# MAX96717_EVB_revC.net
KiCad netlist of a schematic drawn in Altium Designer
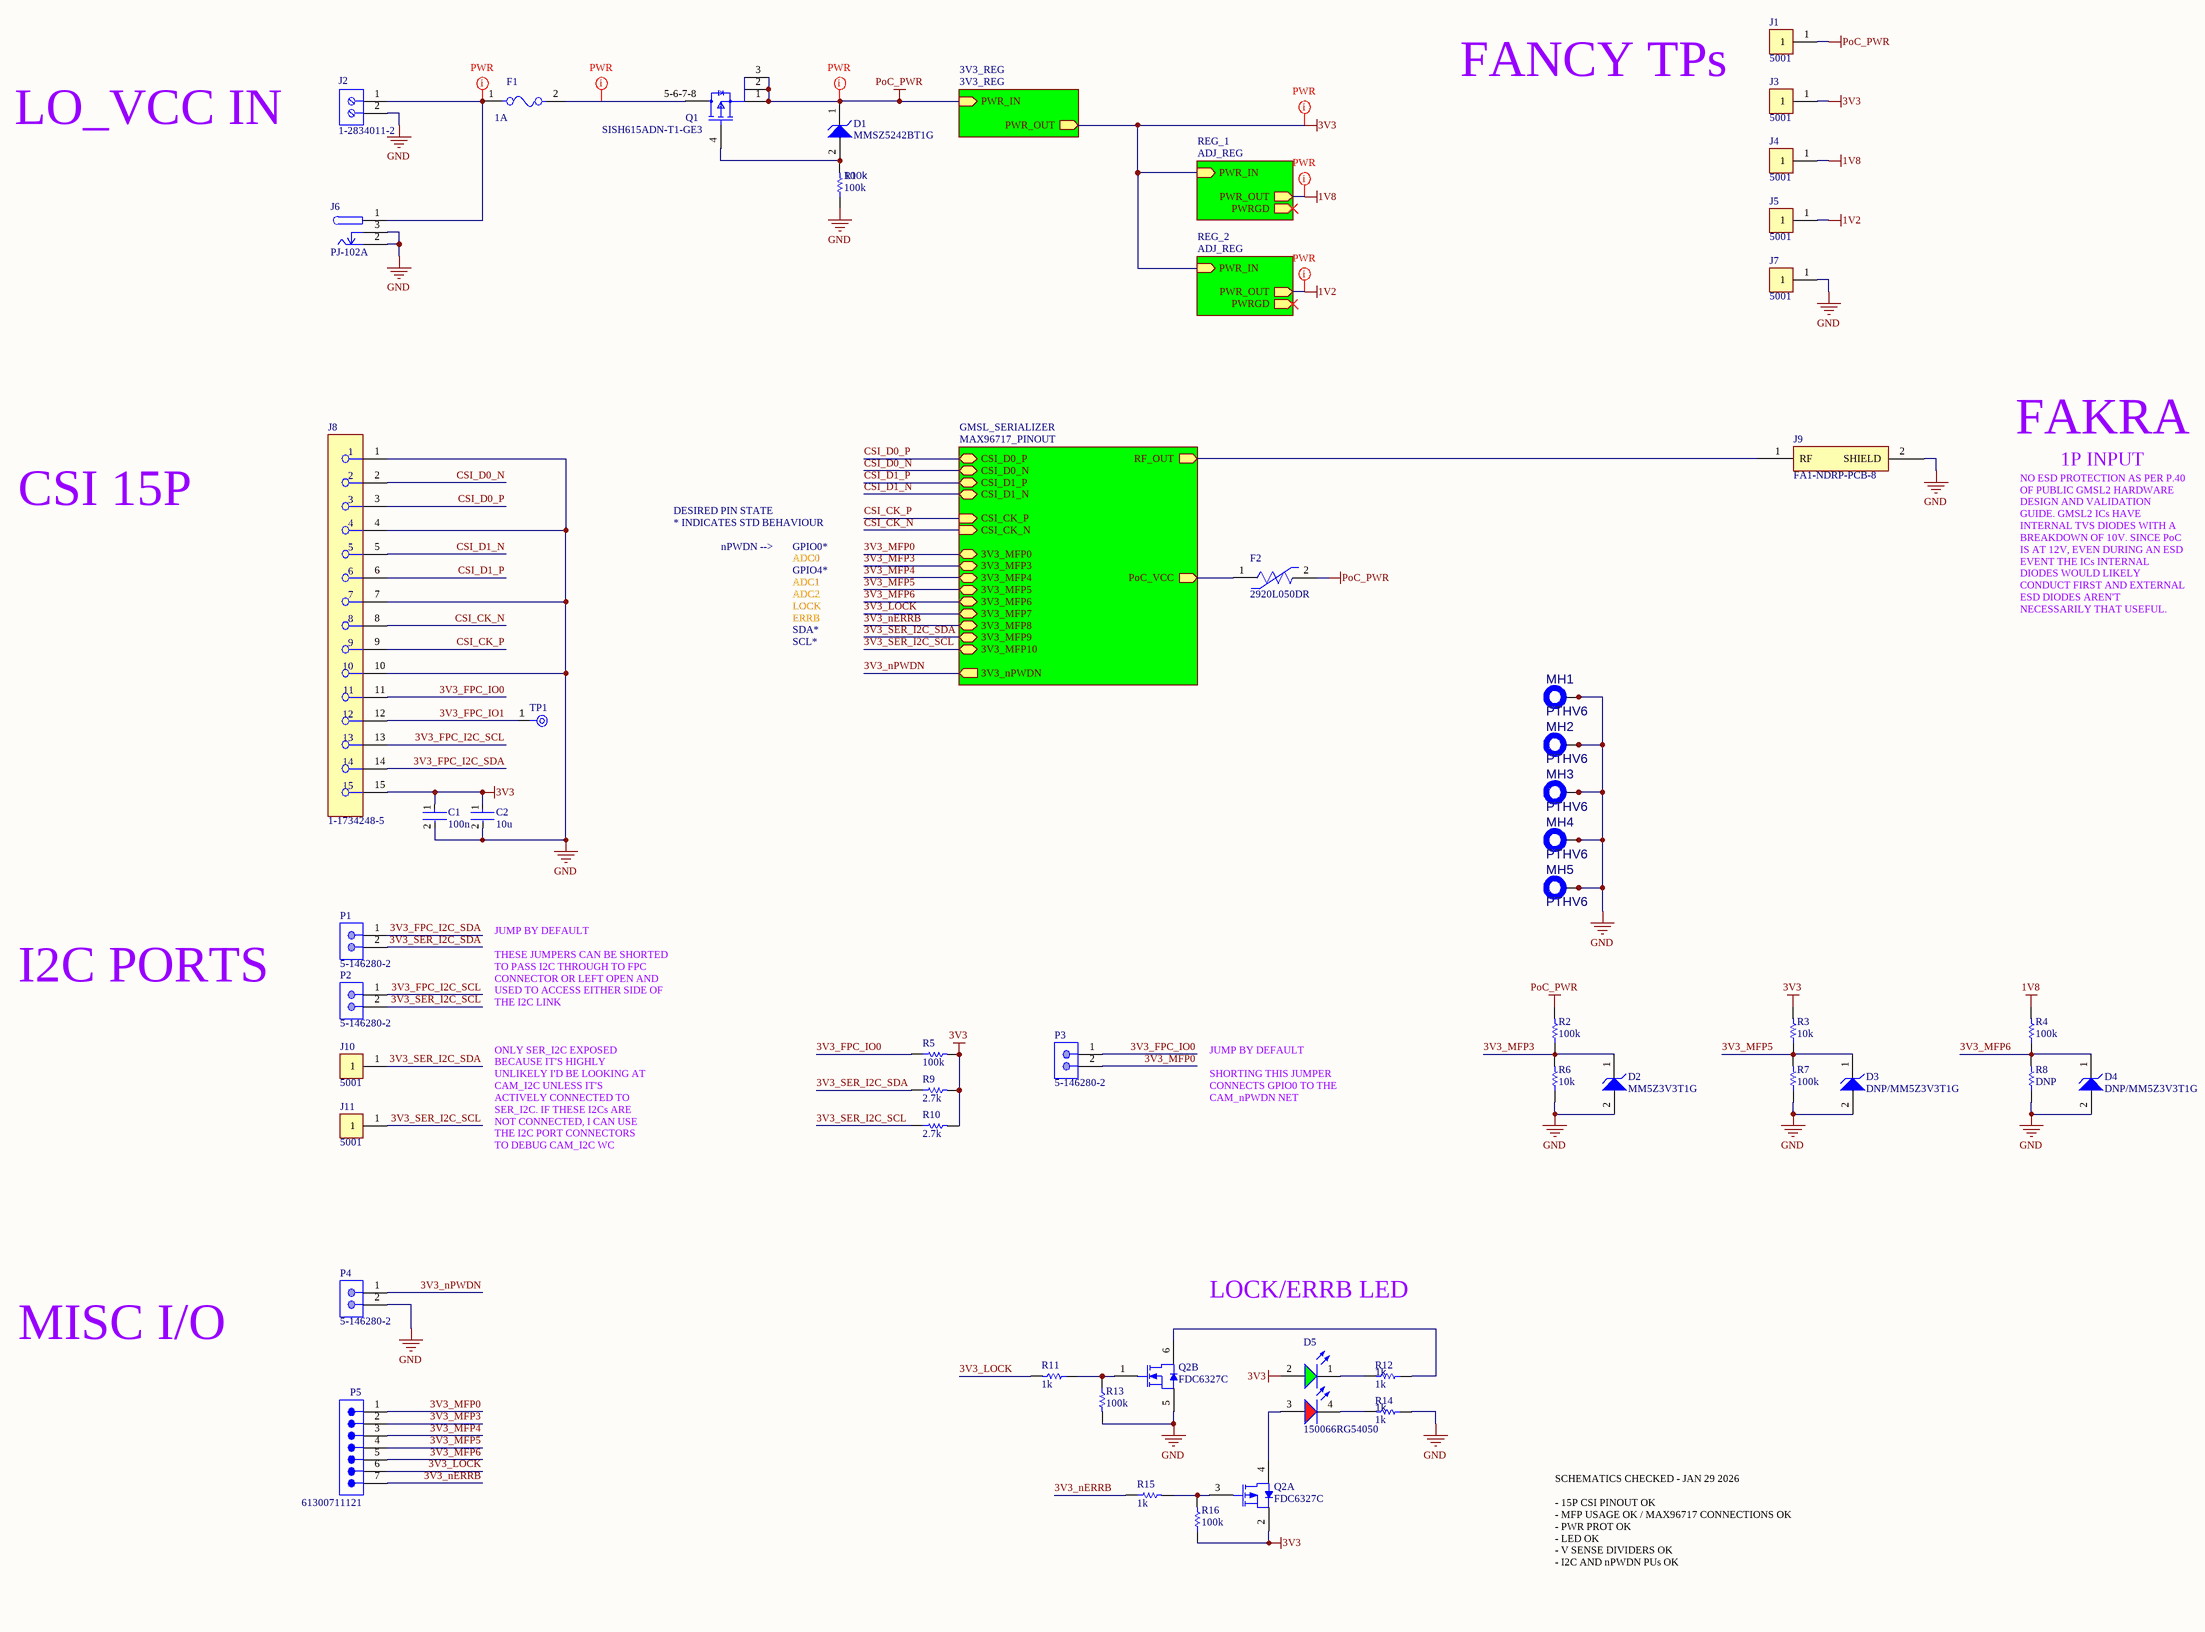
[diagram p0: MAX96717_EVB_revC.SchDoc]

(export (version "E")
  (design (tool "Eeschema 10.0.6"))
  (components
    (comp (ref "C1")
      (value "100n")
      (footprint "FP-0402-L_1_0_0_05-W_0_5-IPC_A")
      (description "LARGE PADS, 0402 CAP, CHANGE COMMENT TO MATCH REAL P/N")
      (libsource (lib "Space Concordia") (part "b4654b650e69147ec39a6b967a45e02"))
    )
    (comp (ref "C2")
      (value "10u")
      (footprint "FP-0402-L_1_0_0_05-W_0_5-IPC_A")
      (description "LARGE PADS, 0402 CAP, CHANGE COMMENT TO MATCH REAL P/N")
      (libsource (lib "Space Concordia") (part "b4654b650e69147ec39a6b967a45e02"))
    )
    (comp (ref "D1")
      (value "MMSZ5242BT1G")
      (footprint "ONSC-SOD-123-2-425-04_V")
      (description "Zener Voltage Regulator, 500 mW, 2-Pin SOD-123, Pb-Free, Tape and Reel")
      (fields (field (name "MANUFACTURER") "On Semiconductor"))
      (libsource (lib "Altium Content Vault") (part "ONSC-K1A2-2"))
    )
    (comp (ref "D2")
      (value "MM5Z3V3T1G")
      (footprint "ONSC-SOD-523-2-502-01_V")
      (description "Zener Voltage Regulator, 500 mW, 2-Pin SOD-523, Pb-Free, Tape and Reel")
      (fields (field (name "MANUFACTURER") "On Semiconductor"))
      (libsource (lib "Altium Content Vault") (part "ONSC-K1A2-2"))
    )
    (comp (ref "D3")
      (value "DNP/MM5Z3V3T1G")
      (footprint "ONSC-SOD-523-2-502-01_V")
      (description "Zener Voltage Regulator, 500 mW, 2-Pin SOD-523, Pb-Free, Tape and Reel")
      (fields (field (name "MANUFACTURER") "On Semiconductor") (field (name "PARTNUMBER") "MM5Z3V3T1G"))
      (libsource (lib "Altium Content Vault") (part "ONSC-K1A2-2"))
    )
    (comp (ref "D4")
      (value "DNP/MM5Z3V3T1G")
      (footprint "ONSC-SOD-523-2-502-01_V")
      (description "Zener Voltage Regulator, 500 mW, 2-Pin SOD-523, Pb-Free, Tape and Reel")
      (fields (field (name "MANUFACTURER") "On Semiconductor") (field (name "PARTNUMBER") "MM5Z3V3T1G"))
      (libsource (lib "Altium Content Vault") (part "ONSC-K1A2-2"))
    )
    (comp (ref "D5")
      (value "150066RG54050")
      (footprint "WL-SBCD_0606")
      (description "Led, Red/Grn, 180Mcd/230Mcd, 624Nm/525Nm Rohs Compliant: Yes")
      (fields (field (name "SOURCE") "rgled.SchLib"))
      (libsource (lib "Space Concordia") (part "CMP-004-00034-2"))
    )
    (comp (ref "F1")
      (value "1A")
      (footprint "FP-SF-1206FP-MFG")
      (description "FUSE BOARD MOUNT 2A 63VDC 1206")
      (libsource (lib "Altium Content Vault") (part "5bcf9b9f640e542cf0359d10258e979"))
    )
    (comp (ref "F2")
      (value "2920L050DR")
      (footprint "FP-2920L050DR-MFG")
      (description "PTC RESET FUSE 60V 500MA 2920")
      (libsource (lib "Altium Content Vault") (part "1c6d77a0208143737455a0c7eb396be"))
    )
    (comp (ref "J1")
      (value "5001")
      (footprint "FP-5001-MFG")
      (description "PC TEST POINT MINIATURE BLACK")
      (libsource (lib "Altium Content Vault") (part "1e4615820a309e3ce90f9e6d957b7fa"))
    )
    (comp (ref "J2")
      (value "1-2834011-2")
      (footprint "1-2834011-2-Footprint-1")
      (description "Barrier Strip Terminal Block")
      (libsource (lib "Space Concordia") (part "1-2834011-2"))
    )
    (comp (ref "J3")
      (value "5001")
      (footprint "FP-5001-MFG")
      (description "PC TEST POINT MINIATURE BLACK")
      (libsource (lib "Altium Content Vault") (part "1e4615820a309e3ce90f9e6d957b7fa"))
    )
    (comp (ref "J4")
      (value "5001")
      (footprint "FP-5001-MFG")
      (description "PC TEST POINT MINIATURE BLACK")
      (libsource (lib "Altium Content Vault") (part "1e4615820a309e3ce90f9e6d957b7fa"))
    )
    (comp (ref "J5")
      (value "5001")
      (footprint "FP-5001-MFG")
      (description "PC TEST POINT MINIATURE BLACK")
      (libsource (lib "Altium Content Vault") (part "1e4615820a309e3ce90f9e6d957b7fa"))
    )
    (comp (ref "J6")
      (value "PJ-102A")
      (footprint "FP-PJ-102A-MFG")
      (description "PJ-102A 2.0 x 6.5 mm, 2.5 A, Horizontal, Through Hole, Tapered Pins, Dc Power Jack Connector")
      (libsource (lib "Altium Content Vault") (part "c639f672d24b5d70918fa8d934b95d1"))
    )
    (comp (ref "J7")
      (value "5001")
      (footprint "FP-5001-MFG")
      (description "PC TEST POINT MINIATURE BLACK")
      (libsource (lib "Altium Content Vault") (part "1e4615820a309e3ce90f9e6d957b7fa"))
    )
    (comp (ref "J8")
      (value "1-1734248-5")
      (footprint "FP-1-1734248-5-MFG")
      (description "CONN FPC VERT 15POS 1.00MM SMD")
      (fields
        (field (name "MANUFACTURER") "TE")
        (field (name "OCTOPART") "https://octopart.com/1-1734248-5-te+connectivity-40620898")
      )
      (libsource (lib "Altium Content Vault") (part "a0777be16b290adccad2a8f9338c195"))
    )
    (comp (ref "J9")
      (value "FA1-NDRP-PCB-8")
      (footprint "FA1-NDRP-PCB-8-Footprint-1")
      (description "RF F Connector, Male, Board Mount, Solder Terminal, Plug")
      (libsource (lib "Space Concordia") (part "FA1-NDRP-PCB-8"))
    )
    (comp (ref "J10")
      (value "5001")
      (footprint "FP-5001-MFG")
      (description "PC TEST POINT MINIATURE BLACK")
      (libsource (lib "Altium Content Vault") (part "1e4615820a309e3ce90f9e6d957b7fa"))
    )
    (comp (ref "J11")
      (value "5001")
      (footprint "FP-5001-MFG")
      (description "PC TEST POINT MINIATURE BLACK")
      (libsource (lib "Altium Content Vault") (part "1e4615820a309e3ce90f9e6d957b7fa"))
    )
    (comp (ref "MH1")
      (value "PTHV6")
      (footprint "PTHV6 M2")
      (libsource (lib "Space Concordia") (part "PTHV6"))
    )
    (comp (ref "MH2")
      (value "PTHV6")
      (footprint "PTHV6 M2")
      (libsource (lib "Space Concordia") (part "PTHV6"))
    )
    (comp (ref "MH3")
      (value "PTHV6")
      (footprint "PTHV6 M2")
      (libsource (lib "Space Concordia") (part "PTHV6"))
    )
    (comp (ref "MH4")
      (value "PTHV6")
      (footprint "PTHV6 M2")
      (libsource (lib "Space Concordia") (part "PTHV6"))
    )
    (comp (ref "MH5")
      (value "PTHV6")
      (footprint "PTHV6 M2")
      (libsource (lib "Space Concordia") (part "PTHV6"))
    )
    (comp (ref "P1")
      (value "5-146280-2")
      (footprint "TECO-5-146280-2_V")
      (fields (field (name "MANUFACTURER") "TE Connectivity"))
      (libsource (lib "Altium Content Vault") (part "CN-1P-M-R2"))
    )
    (comp (ref "P2")
      (value "5-146280-2")
      (footprint "TECO-5-146280-2_V")
      (fields (field (name "MANUFACTURER") "TE Connectivity"))
      (libsource (lib "Altium Content Vault") (part "CN-1P-M-R2"))
    )
    (comp (ref "P3")
      (value "5-146280-2")
      (footprint "TECO-5-146280-2_V")
      (fields (field (name "MANUFACTURER") "TE Connectivity"))
      (libsource (lib "Altium Content Vault") (part "CN-1P-M-R2"))
    )
    (comp (ref "P4")
      (value "5-146280-2")
      (footprint "TECO-5-146280-2_V")
      (fields (field (name "MANUFACTURER") "TE Connectivity"))
      (libsource (lib "Altium Content Vault") (part "CN-1P-M-R2"))
    )
    (comp (ref "P5")
      (value "61300711121")
      (footprint "61300711121")
      (description "THT Vertical Pin Header WR-PHD, Pitch 2.54 mm, Single Row, 7 pins")
      (libsource (lib "Altium Content Vault") (part "Header_Male_1R_07P"))
    )
    (comp (ref "Q1")
      (value "SISH615ADN-T1-GE3")
      (footprint "SISH615ADN-T1-GE3-Footprint-1")
      (description "Trans MOSFET P-CH 20V 22.1A 8-Pin PowerPAK 1212 EP T/R")
      (libsource (lib "Space Concordia") (part "CMP-013-00036-4"))
    )
    (comp (ref "Q2")
      (value "FDC6327C")
      (footprint "FAIR-SOT23-6_V")
      (fields (field (name "MANUFACTURER") "Fairchild"))
      (libsource (lib "Altium Content Vault") (part "PEMOS-SGD-NEMOS-GSD-6"))
    )
    (comp (ref "R1")
      (value "100k")
      (footprint "R0603B")
      (description "Resistor")
      (fields (field (name "ALTIUM_VALUE") "100k"))
      (libsource (lib "Space Concordia") (part "Resistor"))
    )
    (comp (ref "R2")
      (value "100k")
      (footprint "R0603B")
      (description "Resistor")
      (libsource (lib "Space Concordia") (part "Resistor"))
    )
    (comp (ref "R3")
      (value "10k")
      (footprint "R0603B")
      (description "Resistor")
      (libsource (lib "Space Concordia") (part "Resistor"))
    )
    (comp (ref "R4")
      (value "100k")
      (footprint "R0603B")
      (description "Resistor")
      (libsource (lib "Space Concordia") (part "Resistor"))
    )
    (comp (ref "R5")
      (value "100k")
      (footprint "R0603B")
      (description "Resistor")
      (libsource (lib "Space Concordia") (part "Resistor"))
    )
    (comp (ref "R6")
      (value "10k")
      (footprint "R0603B")
      (description "Resistor")
      (libsource (lib "Space Concordia") (part "Resistor"))
    )
    (comp (ref "R7")
      (value "100k")
      (footprint "R0603B")
      (description "Resistor")
      (libsource (lib "Space Concordia") (part "Resistor"))
    )
    (comp (ref "R8")
      (value "DNP")
      (footprint "R0603B")
      (description "Resistor")
      (libsource (lib "Space Concordia") (part "Resistor"))
    )
    (comp (ref "R9")
      (value "2.7k")
      (footprint "R0603B")
      (description "Resistor")
      (libsource (lib "Space Concordia") (part "Resistor"))
    )
    (comp (ref "R10")
      (value "2.7k")
      (footprint "R0603B")
      (description "Resistor")
      (libsource (lib "Space Concordia") (part "Resistor"))
    )
    (comp (ref "R11")
      (value "1k")
      (footprint "R0603B")
      (description "Resistor")
      (libsource (lib "Space Concordia") (part "Resistor"))
    )
    (comp (ref "R12")
      (value "1k")
      (footprint "R0603B")
      (description "Resistor")
      (fields (field (name "ALTIUM_VALUE") "1k"))
      (libsource (lib "Space Concordia") (part "Resistor"))
    )
    (comp (ref "R13")
      (value "100k")
      (footprint "R0603B")
      (description "Resistor")
      (libsource (lib "Space Concordia") (part "Resistor"))
    )
    (comp (ref "R14")
      (value "1k")
      (footprint "R0603B")
      (description "Resistor")
      (fields (field (name "ALTIUM_VALUE") "1k"))
      (libsource (lib "Space Concordia") (part "Resistor"))
    )
    (comp (ref "R15")
      (value "1k")
      (footprint "R0603B")
      (description "Resistor")
      (libsource (lib "Space Concordia") (part "Resistor"))
    )
    (comp (ref "R16")
      (value "100k")
      (footprint "R0603B")
      (description "Resistor")
      (libsource (lib "Space Concordia") (part "Resistor"))
    )
    (comp (ref "TP1")
      (value "TPAD6R")
      (footprint "New footprint 1")
      (description "Test Point .6mm")
      (libsource (lib "Space Concordia") (part "TP"))
    )
  )
  (nets
    (net (code "1") (name "/3V3_FPC_I2C_SCL") (class "Default")
      (node (ref "J8") (pin "13") (pinfunction "13_13") (pintype "passive"))
      (node (ref "P2") (pin "1") (pinfunction "1_1") (pintype "passive"))
    )
    (net (code "2") (name "/3V3_FPC_I2C_SDA") (class "Default")
      (node (ref "J8") (pin "14") (pinfunction "14_14") (pintype "passive"))
      (node (ref "P1") (pin "1") (pinfunction "1_1") (pintype "passive"))
    )
    (net (code "3") (name "/3V3_FPC_IO0") (class "Default")
      (node (ref "J8") (pin "11") (pinfunction "11_11") (pintype "passive"))
      (node (ref "P3") (pin "1") (pinfunction "1_1") (pintype "passive"))
      (node (ref "R5") (pin "1") (pinfunction "1_1") (pintype "passive"))
    )
    (net (code "4") (name "/3V3_FPC_IO1") (class "Default")
      (node (ref "J8") (pin "12") (pinfunction "12_12") (pintype "passive"))
      (node (ref "TP1") (pin "1") (pinfunction "TP_1") (pintype "passive"))
    )
    (net (code "5") (name "/3V3_LOCK") (class "Default")
      (node (ref "P5") (pin "6") (pinfunction "6_6") (pintype "passive"))
      (node (ref "R11") (pin "2") (pinfunction "2_2") (pintype "passive"))
    )
    (net (code "6") (name "/3V3_MFP0") (class "Default")
      (node (ref "P3") (pin "2") (pinfunction "2_2") (pintype "passive"))
      (node (ref "P5") (pin "1") (pinfunction "1_1") (pintype "passive"))
    )
    (net (code "7") (name "/3V3_MFP3") (class "Default")
      (node (ref "D2") (pin "1") (pinfunction "K_1") (pintype "passive"))
      (node (ref "P5") (pin "2") (pinfunction "2_2") (pintype "passive"))
      (node (ref "R2") (pin "1") (pinfunction "1_1") (pintype "passive"))
      (node (ref "R6") (pin "2") (pinfunction "2_2") (pintype "passive"))
    )
    (net (code "8") (name "/3V3_MFP4") (class "Default")
      (node (ref "P5") (pin "3") (pinfunction "3_3") (pintype "passive"))
    )
    (net (code "9") (name "/3V3_MFP5") (class "Default")
      (node (ref "D3") (pin "1") (pinfunction "K_1") (pintype "passive"))
      (node (ref "P5") (pin "4") (pinfunction "4_4") (pintype "passive"))
      (node (ref "R3") (pin "1") (pinfunction "1_1") (pintype "passive"))
      (node (ref "R7") (pin "2") (pinfunction "2_2") (pintype "passive"))
    )
    (net (code "10") (name "/3V3_MFP6") (class "Default")
      (node (ref "D4") (pin "1") (pinfunction "K_1") (pintype "passive"))
      (node (ref "P5") (pin "5") (pinfunction "5_5") (pintype "passive"))
      (node (ref "R4") (pin "1") (pinfunction "1_1") (pintype "passive"))
      (node (ref "R8") (pin "2") (pinfunction "2_2") (pintype "passive"))
    )
    (net (code "11") (name "/3V3_SER_I2C_SCL") (class "Default")
      (node (ref "J11") (pin "1") (pinfunction "1_1") (pintype "passive"))
      (node (ref "P2") (pin "2") (pinfunction "2_2") (pintype "passive"))
      (node (ref "R10") (pin "1") (pinfunction "1_1") (pintype "passive"))
    )
    (net (code "12") (name "/3V3_SER_I2C_SDA") (class "Default")
      (node (ref "J10") (pin "1") (pinfunction "1_1") (pintype "passive"))
      (node (ref "P1") (pin "2") (pinfunction "2_2") (pintype "passive"))
      (node (ref "R9") (pin "1") (pinfunction "1_1") (pintype "passive"))
    )
    (net (code "13") (name "/3V3_nERRB") (class "Default")
      (node (ref "P5") (pin "7") (pinfunction "7_7") (pintype "passive"))
      (node (ref "R15") (pin "1") (pinfunction "1_1") (pintype "passive"))
    )
    (net (code "14") (name "/3V3_nPWDN") (class "Default")
      (node (ref "P4") (pin "1") (pinfunction "1_1") (pintype "passive"))
    )
    (net (code "15") (name "/CSI_CK_N") (class "Default")
      (node (ref "J8") (pin "8") (pinfunction "8_8") (pintype "passive"))
    )
    (net (code "16") (name "/CSI_CK_P") (class "Default")
      (node (ref "J8") (pin "9") (pinfunction "9_9") (pintype "passive"))
    )
    (net (code "17") (name "/CSI_D0_N") (class "Default")
      (node (ref "J8") (pin "2") (pinfunction "2_2") (pintype "passive"))
    )
    (net (code "18") (name "/CSI_D0_P") (class "Default")
      (node (ref "J8") (pin "3") (pinfunction "3_3") (pintype "passive"))
    )
    (net (code "19") (name "/CSI_D1_N") (class "Default")
      (node (ref "J8") (pin "5") (pinfunction "5_5") (pintype "passive"))
    )
    (net (code "20") (name "/CSI_D1_P") (class "Default")
      (node (ref "J8") (pin "6") (pinfunction "6_6") (pintype "passive"))
    )
    (net (code "23") (name "/PoC_VCC") (class "Default")
      (node (ref "F2") (pin "1") (pinfunction "1_1") (pintype "passive"))
    )
    (net (code "24") (name "/RF_OUT") (class "Default")
      (node (ref "J9") (pin "1") (pinfunction "RF_1") (pintype "passive"))
    )
    (net (code "25") (name "1V2") (class "Default")
      (node (ref "J5") (pin "1") (pinfunction "1_1") (pintype "passive"))
    )
    (net (code "26") (name "1V8") (class "Default")
      (node (ref "J4") (pin "1") (pinfunction "1_1") (pintype "passive"))
      (node (ref "R4") (pin "2") (pinfunction "2_2") (pintype "passive"))
    )
    (net (code "27") (name "3V3") (class "Default")
      (node (ref "C1") (pin "1") (pinfunction "1_1") (pintype "passive"))
      (node (ref "C2") (pin "1") (pinfunction "1_1") (pintype "passive"))
      (node (ref "D5") (pin "2") (pinfunction "A_2") (pintype "passive"))
      (node (ref "J3") (pin "1") (pinfunction "1_1") (pintype "passive"))
      (node (ref "J8") (pin "15") (pinfunction "15_15") (pintype "passive"))
      (node (ref "Q2") (pin "2") (pinfunction "S_2") (pintype "passive"))
      (node (ref "R10") (pin "2") (pinfunction "2_2") (pintype "passive"))
      (node (ref "R16") (pin "1") (pinfunction "1_1") (pintype "passive"))
      (node (ref "R3") (pin "2") (pinfunction "2_2") (pintype "passive"))
      (node (ref "R5") (pin "2") (pinfunction "2_2") (pintype "passive"))
      (node (ref "R9") (pin "2") (pinfunction "2_2") (pintype "passive"))
    )
    (net (code "28") (name "GND") (class "Default")
      (node (ref "C1") (pin "2") (pinfunction "2_2") (pintype "passive"))
      (node (ref "C2") (pin "2") (pinfunction "2_2") (pintype "passive"))
      (node (ref "D2") (pin "2") (pinfunction "A_2") (pintype "passive"))
      (node (ref "D3") (pin "2") (pinfunction "A_2") (pintype "passive"))
      (node (ref "D4") (pin "2") (pinfunction "A_2") (pintype "passive"))
      (node (ref "J2") (pin "2") (pinfunction "2_2") (pintype "passive"))
      (node (ref "J6") (pin "2") (pinfunction "2_2") (pintype "passive"))
      (node (ref "J6") (pin "3") (pinfunction "3_3") (pintype "passive"))
      (node (ref "J7") (pin "1") (pinfunction "1_1") (pintype "passive"))
      (node (ref "J8") (pin "1") (pinfunction "1_1") (pintype "passive"))
      (node (ref "J8") (pin "10") (pinfunction "10_10") (pintype "passive"))
      (node (ref "J8") (pin "4") (pinfunction "4_4") (pintype "passive"))
      (node (ref "J8") (pin "7") (pinfunction "7_7") (pintype "passive"))
      (node (ref "J9") (pin "2") (pinfunction "SHIELD_2") (pintype "passive"))
      (node (ref "MH1") (pin "1") (pinfunction "MH_1") (pintype "passive"))
      (node (ref "MH1") (pin "2") (pinfunction "V1_2") (pintype "passive"))
      (node (ref "MH1") (pin "3") (pinfunction "V2_3") (pintype "passive"))
      (node (ref "MH1") (pin "4") (pinfunction "V3_4") (pintype "passive"))
      (node (ref "MH1") (pin "5") (pinfunction "V4_5") (pintype "passive"))
      (node (ref "MH1") (pin "6") (pinfunction "V5_6") (pintype "passive"))
      (node (ref "MH1") (pin "7") (pinfunction "V6_7") (pintype "passive"))
      (node (ref "MH2") (pin "1") (pinfunction "MH_1") (pintype "passive"))
      (node (ref "MH2") (pin "2") (pinfunction "V1_2") (pintype "passive"))
      (node (ref "MH2") (pin "3") (pinfunction "V2_3") (pintype "passive"))
      (node (ref "MH2") (pin "4") (pinfunction "V3_4") (pintype "passive"))
      (node (ref "MH2") (pin "5") (pinfunction "V4_5") (pintype "passive"))
      (node (ref "MH2") (pin "6") (pinfunction "V5_6") (pintype "passive"))
      (node (ref "MH2") (pin "7") (pinfunction "V6_7") (pintype "passive"))
      (node (ref "MH3") (pin "1") (pinfunction "MH_1") (pintype "passive"))
      (node (ref "MH3") (pin "2") (pinfunction "V1_2") (pintype "passive"))
      (node (ref "MH3") (pin "3") (pinfunction "V2_3") (pintype "passive"))
      (node (ref "MH3") (pin "4") (pinfunction "V3_4") (pintype "passive"))
      (node (ref "MH3") (pin "5") (pinfunction "V4_5") (pintype "passive"))
      (node (ref "MH3") (pin "6") (pinfunction "V5_6") (pintype "passive"))
      (node (ref "MH3") (pin "7") (pinfunction "V6_7") (pintype "passive"))
      (node (ref "MH4") (pin "1") (pinfunction "MH_1") (pintype "passive"))
      (node (ref "MH4") (pin "2") (pinfunction "V1_2") (pintype "passive"))
      (node (ref "MH4") (pin "3") (pinfunction "V2_3") (pintype "passive"))
      (node (ref "MH4") (pin "4") (pinfunction "V3_4") (pintype "passive"))
      (node (ref "MH4") (pin "5") (pinfunction "V4_5") (pintype "passive"))
      (node (ref "MH4") (pin "6") (pinfunction "V5_6") (pintype "passive"))
      (node (ref "MH4") (pin "7") (pinfunction "V6_7") (pintype "passive"))
      (node (ref "MH5") (pin "1") (pinfunction "MH_1") (pintype "passive"))
      (node (ref "MH5") (pin "2") (pinfunction "V1_2") (pintype "passive"))
      (node (ref "MH5") (pin "3") (pinfunction "V2_3") (pintype "passive"))
      (node (ref "MH5") (pin "4") (pinfunction "V3_4") (pintype "passive"))
      (node (ref "MH5") (pin "5") (pinfunction "V4_5") (pintype "passive"))
      (node (ref "MH5") (pin "6") (pinfunction "V5_6") (pintype "passive"))
      (node (ref "MH5") (pin "7") (pinfunction "V6_7") (pintype "passive"))
      (node (ref "P4") (pin "2") (pinfunction "2_2") (pintype "passive"))
      (node (ref "Q2") (pin "5") (pinfunction "S_5") (pintype "passive"))
      (node (ref "R1") (pin "1") (pinfunction "1_1") (pintype "passive"))
      (node (ref "R13") (pin "2") (pinfunction "2_2") (pintype "passive"))
      (node (ref "R14") (pin "1") (pinfunction "1_1") (pintype "passive"))
      (node (ref "R6") (pin "1") (pinfunction "1_1") (pintype "passive"))
      (node (ref "R7") (pin "1") (pinfunction "1_1") (pintype "passive"))
      (node (ref "R8") (pin "1") (pinfunction "1_1") (pintype "passive"))
    )
    (net (code "29") (name "Net-(D1-A)") (class "Default")
      (node (ref "D1") (pin "2") (pinfunction "A_2") (pintype "passive"))
      (node (ref "Q1") (pin "4") (pinfunction "G_4") (pintype "passive"))
      (node (ref "R1") (pin "2") (pinfunction "2_2") (pintype "passive"))
    )
    (net (code "30") (name "Net-(D5-K-Pad1)") (class "Default")
      (node (ref "D5") (pin "1") (pinfunction "K_1") (pintype "passive"))
      (node (ref "R12") (pin "2") (pinfunction "2_2") (pintype "passive"))
    )
    (net (code "31") (name "Net-(D5-K-Pad4)") (class "Default")
      (node (ref "D5") (pin "4") (pinfunction "K_4") (pintype "passive"))
      (node (ref "R14") (pin "2") (pinfunction "2_2") (pintype "passive"))
    )
    (net (code "32") (name "Net-(F1-Pad1)") (class "Default")
      (node (ref "F1") (pin "1") (pinfunction "1_1") (pintype "passive"))
      (node (ref "J2") (pin "1") (pinfunction "1_1") (pintype "passive"))
      (node (ref "J6") (pin "1") (pinfunction "1_1") (pintype "passive"))
    )
    (net (code "33") (name "Net-(Q1-D)") (class "Default")
      (node (ref "F1") (pin "2") (pinfunction "2_2") (pintype "passive"))
      (node (ref "Q1") (pin "5-6-7-8") (pinfunction "D_5-6-7-8") (pintype "passive"))
    )
    (net (code "34") (name "Net-(Q2A-D)") (class "Default")
      (node (ref "D5") (pin "3") (pinfunction "A_3") (pintype "passive"))
      (node (ref "Q2") (pin "4") (pinfunction "D_4") (pintype "passive"))
    )
    (net (code "35") (name "Net-(Q2A-G)") (class "Default")
      (node (ref "Q2") (pin "3") (pinfunction "G_3") (pintype "passive"))
      (node (ref "R15") (pin "2") (pinfunction "2_2") (pintype "passive"))
      (node (ref "R16") (pin "2") (pinfunction "2_2") (pintype "passive"))
    )
    (net (code "36") (name "Net-(Q2B-D)") (class "Default")
      (node (ref "Q2") (pin "6") (pinfunction "D_6") (pintype "passive"))
      (node (ref "R12") (pin "1") (pinfunction "1_1") (pintype "passive"))
    )
    (net (code "37") (name "Net-(Q2B-G)") (class "Default")
      (node (ref "Q2") (pin "1") (pinfunction "G_1") (pintype "passive"))
      (node (ref "R11") (pin "1") (pinfunction "1_1") (pintype "passive"))
      (node (ref "R13") (pin "1") (pinfunction "1_1") (pintype "passive"))
    )
    (net (code "38") (name "PoC_PWR") (class "Default")
      (node (ref "D1") (pin "1") (pinfunction "K_1") (pintype "passive"))
      (node (ref "F2") (pin "2") (pinfunction "2_2") (pintype "passive"))
      (node (ref "J1") (pin "1") (pinfunction "1_1") (pintype "passive"))
      (node (ref "Q1") (pin "1") (pinfunction "S_1") (pintype "passive"))
      (node (ref "Q1") (pin "2") (pinfunction "S_2") (pintype "passive"))
      (node (ref "Q1") (pin "3") (pinfunction "S_3") (pintype "passive"))
      (node (ref "R2") (pin "2") (pinfunction "2_2") (pintype "passive"))
    )
  )
)
